# tick-pcf2129t-breakout-mk-1_0.net
KiCad netlist of a schematic drawn in EAGLE
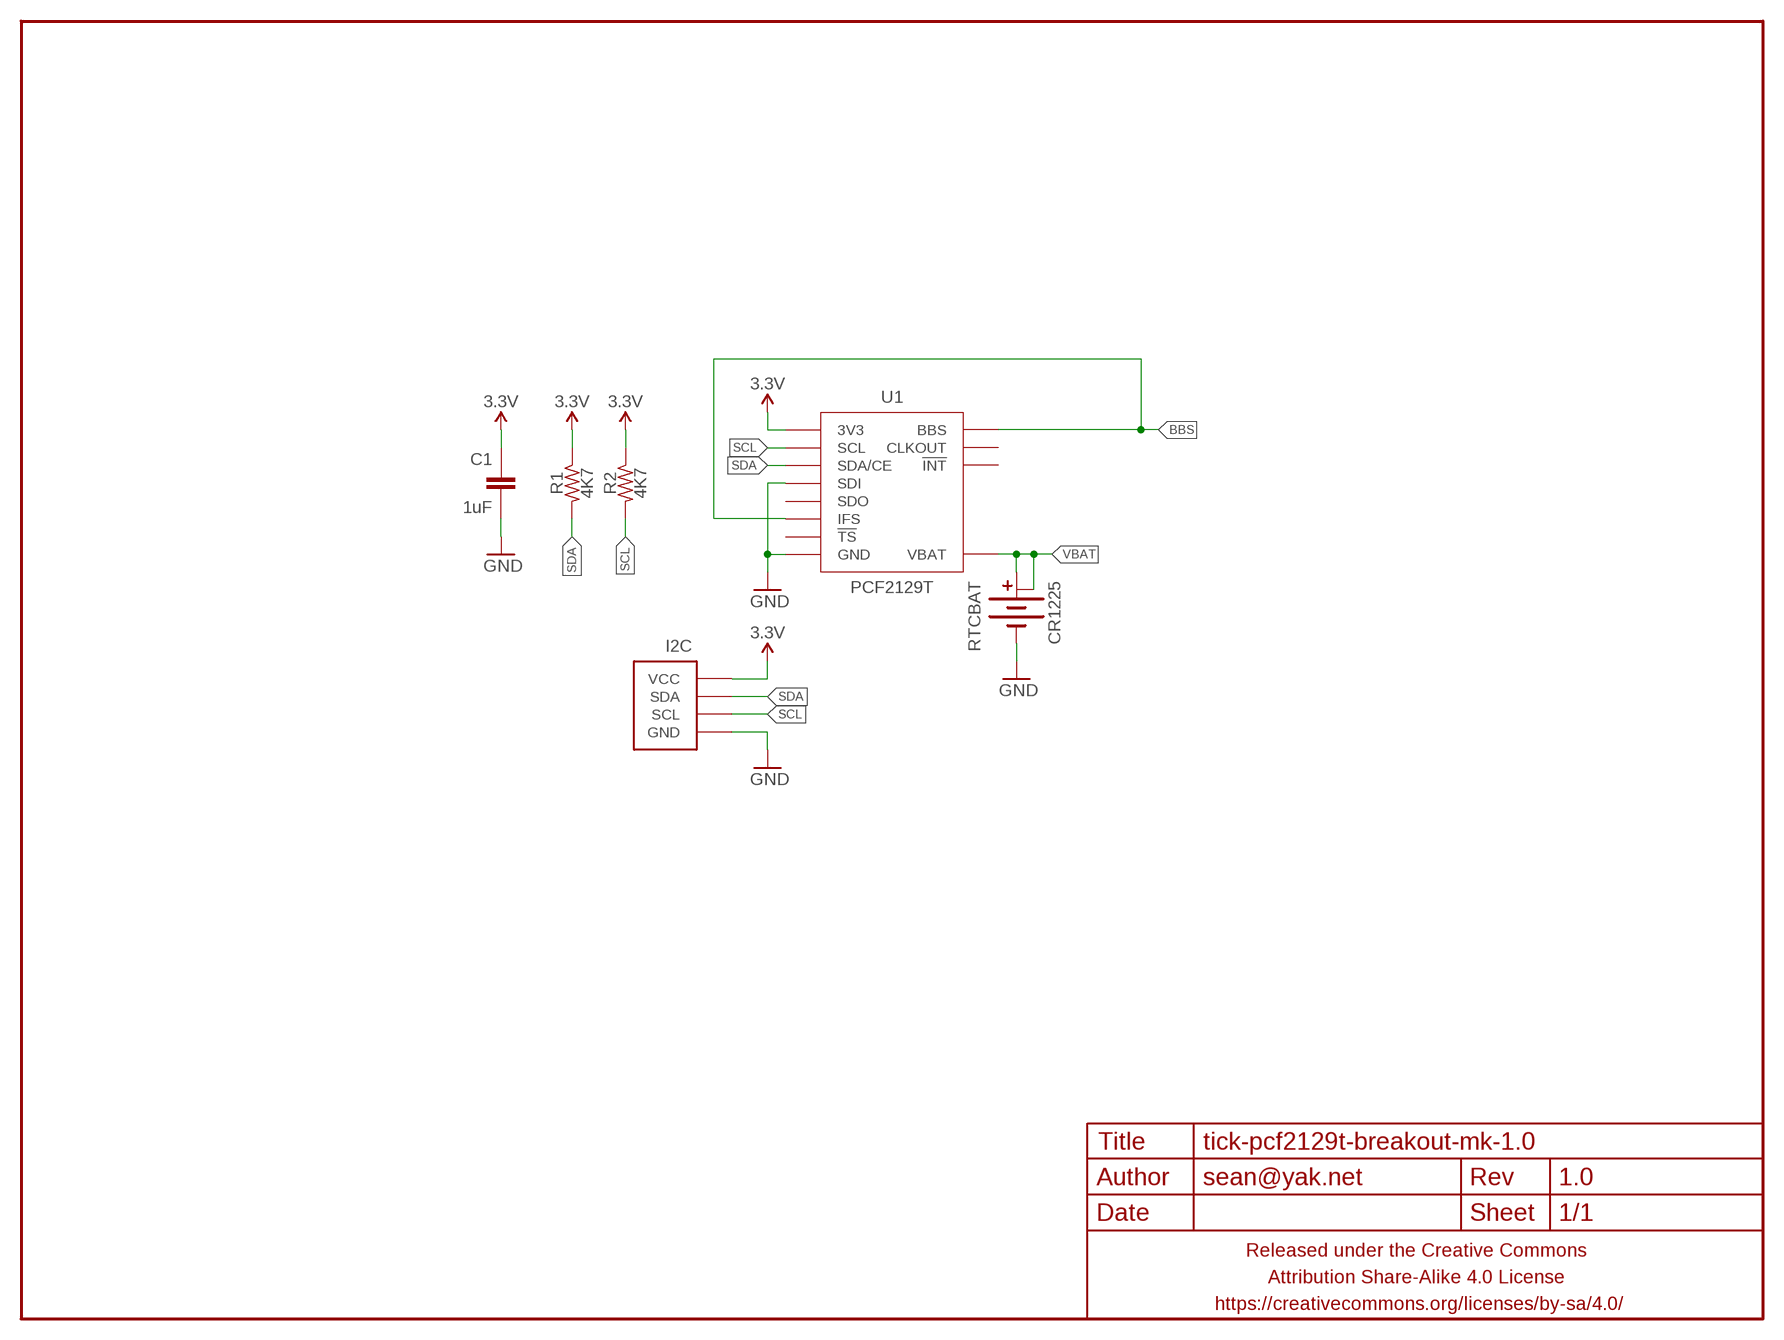
[diagram p0: schematic, sheet 1]

(export (version "E")
  (design (tool "Eeschema 10.0.6"))
  (components
    (comp (ref "C1")
      (value "1uF")
      (footprint "eagle-import:C0603-TIGHTER")
      (libsource (lib "eagle-import") (part "CAPACITOR-CERAMICC0603-TIGHTER"))
    )
    (comp (ref "FRAME1")
      (value "FRAME-LETTERNO_PACKAGE")
      (footprint "eagle-import:DUMMY")
      (fields (field (name "DESIGNER") "sean@yak.net") (field (name "VERSION") "1.0"))
      (libsource (lib "eagle-import") (part "FRAME-LETTERNO_PACKAGE"))
    )
    (comp (ref "I2C")
      (value "M04-I2CPTH-0.1IN-CENTERED")
      (footprint "eagle-import:1X04-PTH-VERT-I2C-CENTERED")
      (libsource (lib "eagle-import") (part "M04-I2CPTH-0.1IN-CENTERED"))
    )
    (comp (ref "R1")
      (value "4K7")
      (footprint "eagle-import:R0603-TIGHTER")
      (libsource (lib "eagle-import") (part "RESISTORR0603-TIGHTER"))
    )
    (comp (ref "R2")
      (value "4K7")
      (footprint "eagle-import:R0603-TIGHTER")
      (libsource (lib "eagle-import") (part "RESISTORR0603-TIGHTER"))
    )
    (comp (ref "RTCBAT")
      (value "CR1225")
      (footprint "eagle-import:BATTCON_12MM_SMD")
      (libsource (lib "eagle-import") (part "BATTERY-COINCR1225_SMD_SMALLER"))
    )
    (comp (ref "U1")
      (value "PCF2129T")
      (footprint "eagle-import:SO16W")
      (libsource (lib "eagle-import") (part "PCF2129SO16W"))
    )
  )
  (nets
    (net (code "1") (name "3.3V") (class "Default")
      (node (ref "C1") (pin "1") (pinfunction "1_1") (pintype "passive"))
      (node (ref "I2C") (pin "VCC") (pinfunction "VCC_VCC") (pintype "bidirectional"))
      (node (ref "R1") (pin "1") (pinfunction "1_1") (pintype "passive"))
      (node (ref "R2") (pin "1") (pinfunction "1_1") (pintype "passive"))
      (node (ref "U1") (pin "16") (pinfunction "3V3_16") (pintype "bidirectional"))
    )
    (net (code "2") (name "BBS") (class "Default")
      (node (ref "U1") (pin "14") (pinfunction "BBS_14") (pintype "bidirectional"))
      (node (ref "U1") (pin "5") (pinfunction "IFS_5") (pintype "bidirectional"))
    )
    (net (code "3") (name "GND") (class "Default")
      (node (ref "C1") (pin "2") (pinfunction "2_2") (pintype "passive"))
      (node (ref "I2C") (pin "GND") (pinfunction "GND_GND") (pintype "bidirectional"))
      (node (ref "RTCBAT") (pin "-") (pinfunction "-_-") (pintype "bidirectional"))
      (node (ref "U1") (pin "2") (pinfunction "SDI_2") (pintype "bidirectional"))
      (node (ref "U1") (pin "8") (pinfunction "GND_8") (pintype "bidirectional"))
    )
    (net (code "4") (name "SCL") (class "Default")
      (node (ref "I2C") (pin "SCL") (pinfunction "SCL_SCL") (pintype "bidirectional"))
      (node (ref "R2") (pin "2") (pinfunction "2_2") (pintype "passive"))
      (node (ref "U1") (pin "1") (pinfunction "SCL_1") (pintype "bidirectional"))
    )
    (net (code "5") (name "SDA") (class "Default")
      (node (ref "I2C") (pin "SDA") (pinfunction "SDA_SDA") (pintype "bidirectional"))
      (node (ref "R1") (pin "2") (pinfunction "2_2") (pintype "passive"))
      (node (ref "U1") (pin "4") (pinfunction "SDA/CE_4") (pintype "bidirectional"))
    )
    (net (code "6") (name "VBAT") (class "Default")
      (node (ref "RTCBAT") (pin "+@1") (pinfunction "+_+@1") (pintype "bidirectional"))
      (node (ref "RTCBAT") (pin "+@2") (pinfunction "+1_+@2") (pintype "bidirectional"))
      (node (ref "U1") (pin "15") (pinfunction "VBAT_15") (pintype "bidirectional"))
    )
    (net (code "7") (name "unconnected-(U1-CLKOUT-Pad7)") (class "Default")
      (node (ref "U1") (pin "7") (pinfunction "CLKOUT_7") (pintype "bidirectional"))
    )
    (net (code "8") (name "unconnected-(U1-SDO-Pad3)") (class "Default")
      (node (ref "U1") (pin "3") (pinfunction "SDO_3") (pintype "bidirectional"))
    )
    (net (code "9") (name "unconnected-(U1-~{INT}-Pad13)") (class "Default")
      (node (ref "U1") (pin "13") (pinfunction "~{INT}_13") (pintype "bidirectional"))
    )
    (net (code "10") (name "unconnected-(U1-~{TS}-Pad6)") (class "Default")
      (node (ref "U1") (pin "6") (pinfunction "~{TS}_6") (pintype "bidirectional"))
    )
  )
)
